# SCH_PCB-device_2024-08-12.net
KiCad netlist of a schematic drawn in EasyEDA
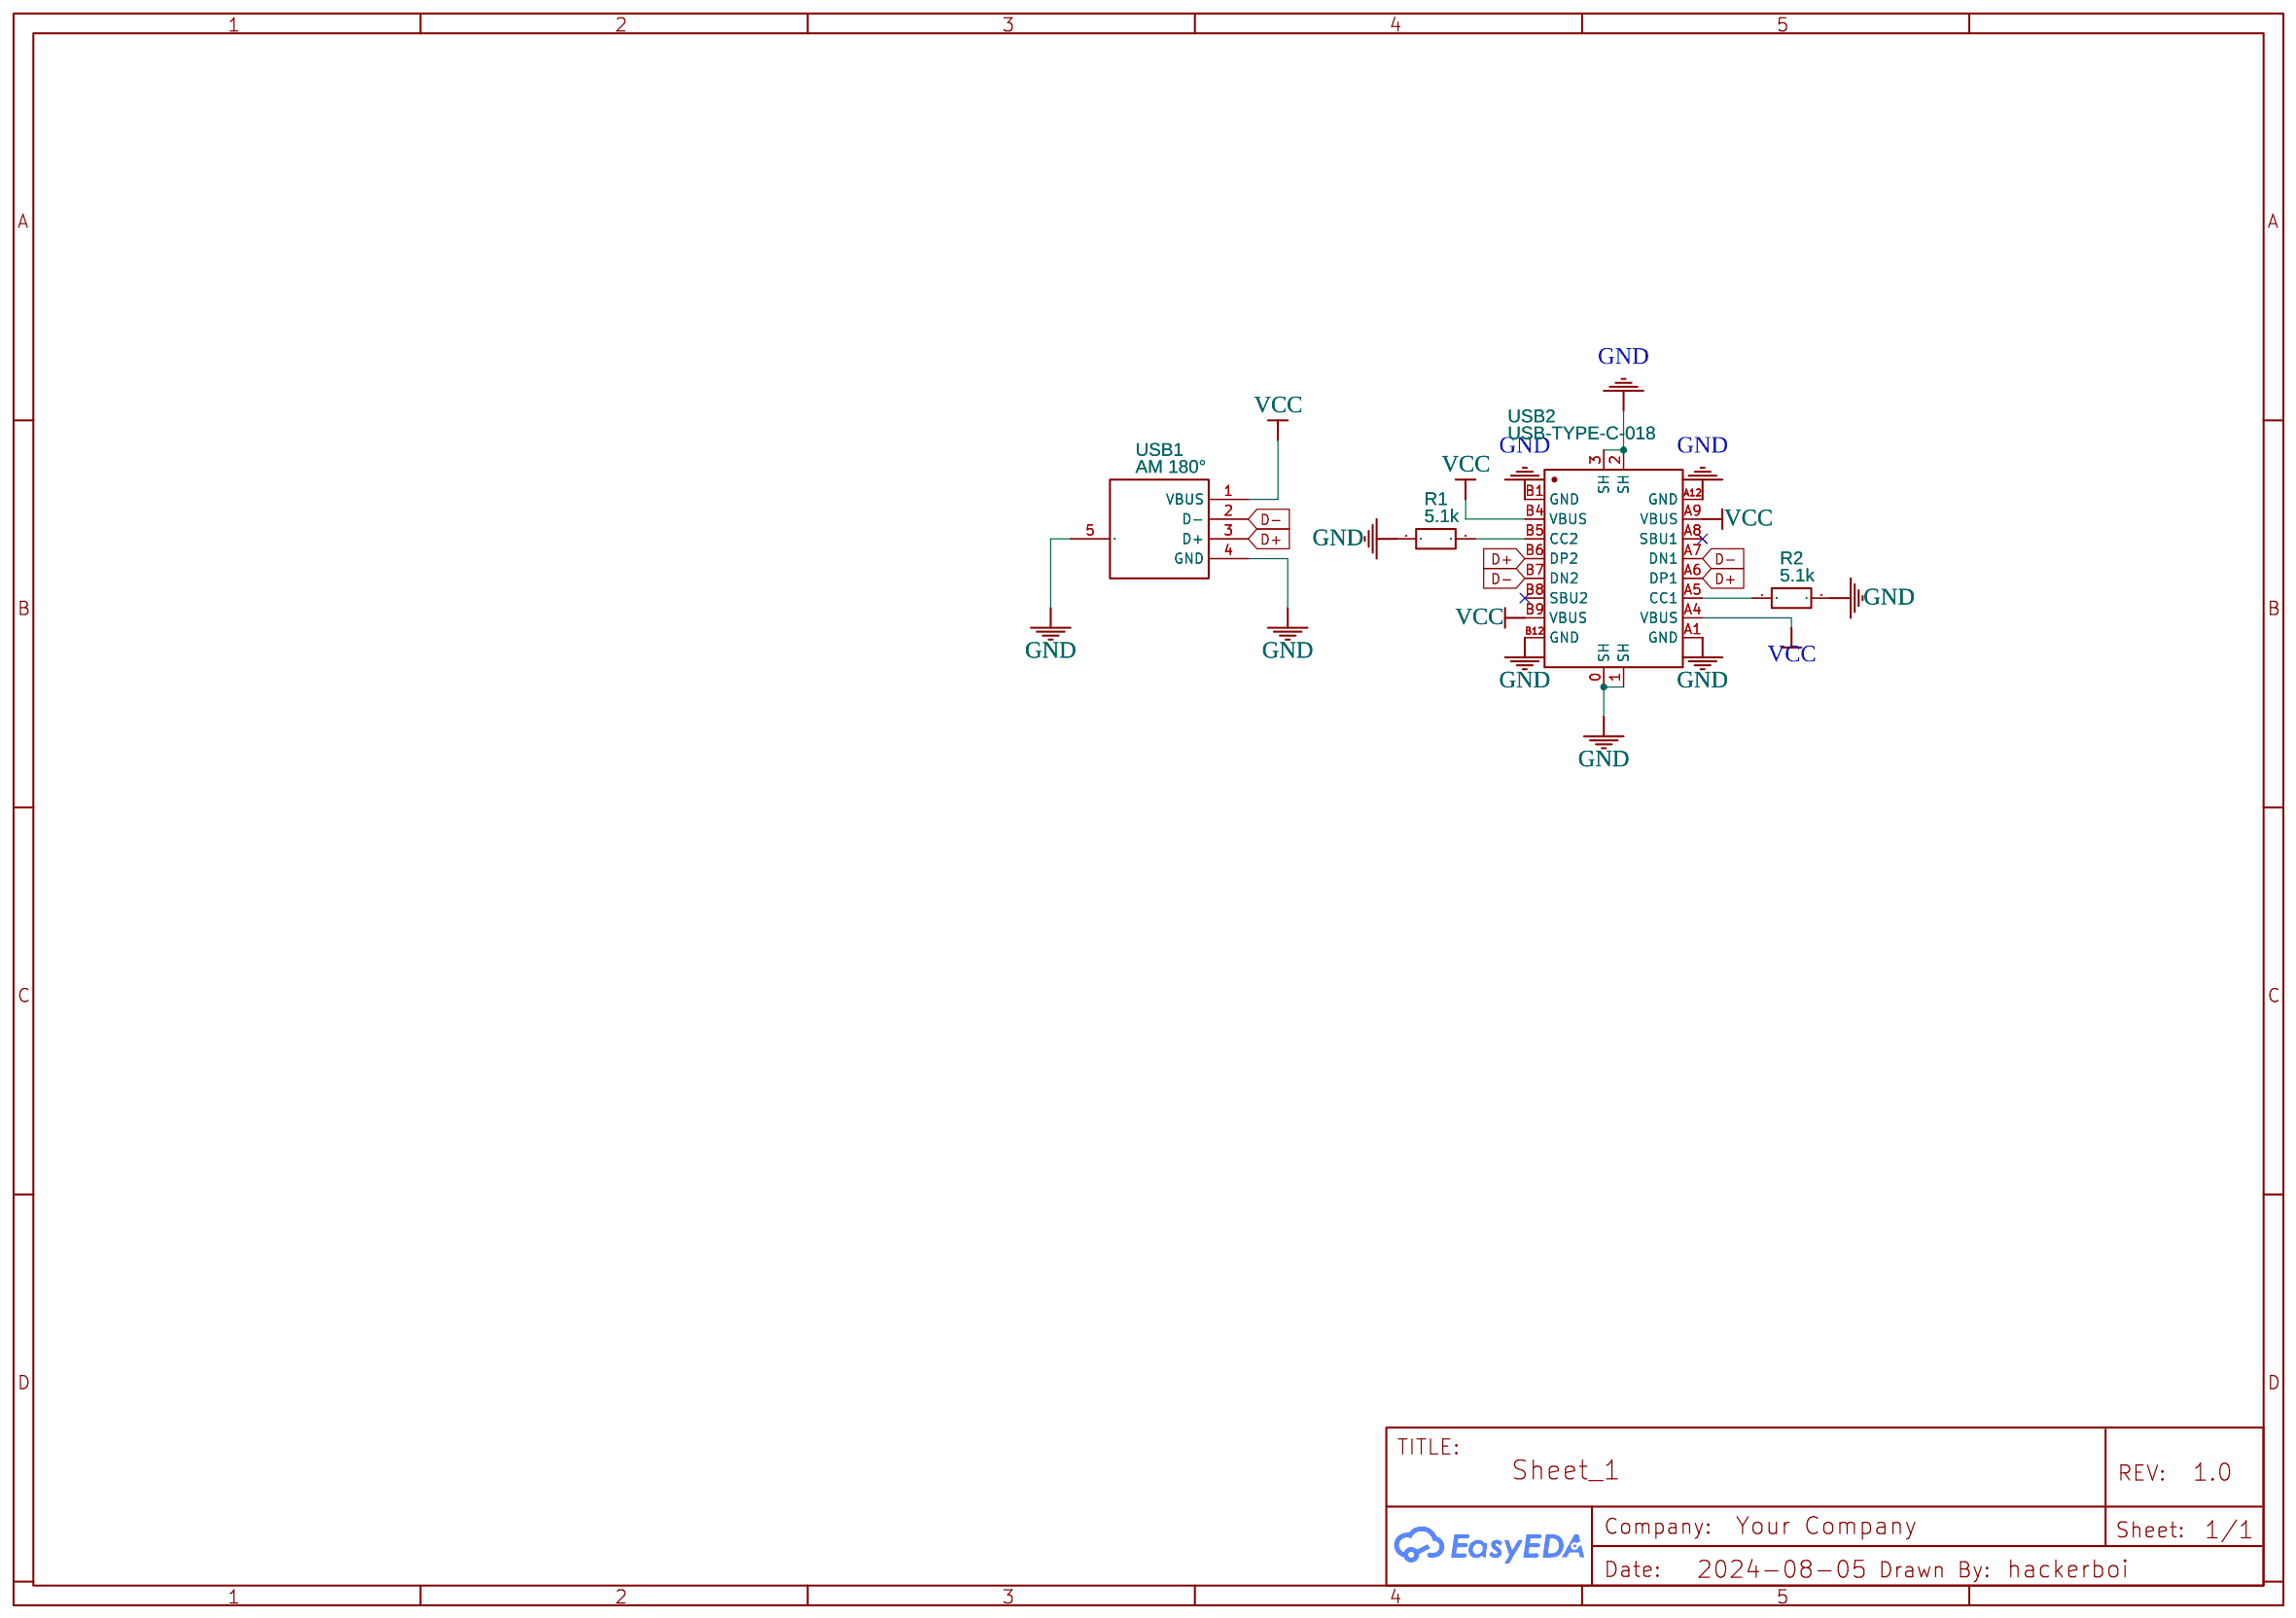
[diagram p0: schematic sheet]

(export (version "E")
  (design (tool "Eeschema 10.0.6"))
  (components
    (comp (ref "R1") (value "5.1k") (libsource (lib "") (part "R_0603_EU")))
    (comp (ref "R2") (value "5.1k") (libsource (lib "") (part "R_0603_EU")))
    (comp (ref "USB1")
      (value "AM 180°")
      (fields (field (name "Manufacturer") "SHOU HAN(首韩)"))
      (libsource (lib "") (part "AM 180°"))
    )
    (comp (ref "USB2")
      (value "USB-TYPE-C-018")
      (fields (field (name "Manufacturer") "DEALON(德艺隆)"))
      (libsource (lib "") (part "USB-TYPE-C-018"))
    )
  )
  (nets
    (net (code "1") (name "D+") (class "Default")
      (node (ref "USB1") (pin "3") (pinfunction "D+_3") (pintype "input"))
      (node (ref "USB2") (pin "A6") (pinfunction "DP1_A6") (pintype "unspecified"))
      (node (ref "USB2") (pin "B6") (pinfunction "DP2_B6") (pintype "unspecified"))
    )
    (net (code "2") (name "D-") (class "Default")
      (node (ref "USB1") (pin "2") (pinfunction "D-_2") (pintype "input"))
      (node (ref "USB2") (pin "A7") (pinfunction "DN1_A7") (pintype "unspecified"))
      (node (ref "USB2") (pin "B7") (pinfunction "DN2_B7") (pintype "unspecified"))
    )
    (net (code "3") (name "GND") (class "Default")
      (node (ref "R1") (pin "1") (pinfunction "1_1") (pintype "unspecified"))
      (node (ref "R2") (pin "2") (pinfunction "2_2") (pintype "unspecified"))
      (node (ref "USB1") (pin "4") (pinfunction "GND_4") (pintype "input"))
      (node (ref "USB1") (pin "5") (pinfunction "EH_5") (pintype "input"))
      (node (ref "USB2") (pin "0") (pinfunction "SH_0") (pintype "unspecified"))
      (node (ref "USB2") (pin "1") (pinfunction "SH_1") (pintype "unspecified"))
      (node (ref "USB2") (pin "2") (pinfunction "SH_2") (pintype "unspecified"))
      (node (ref "USB2") (pin "3") (pinfunction "SH_3") (pintype "unspecified"))
      (node (ref "USB2") (pin "A1") (pinfunction "GND_A1") (pintype "unspecified"))
      (node (ref "USB2") (pin "A12") (pinfunction "GND_A12") (pintype "unspecified"))
      (node (ref "USB2") (pin "B1") (pinfunction "GND_B1") (pintype "unspecified"))
      (node (ref "USB2") (pin "B12") (pinfunction "GND_B12") (pintype "unspecified"))
    )
    (net (code "4") (name "Net-(USB2-CC1)") (class "Default")
      (node (ref "R2") (pin "1") (pinfunction "1_1") (pintype "unspecified"))
      (node (ref "USB2") (pin "A5") (pinfunction "CC1_A5") (pintype "unspecified"))
    )
    (net (code "5") (name "Net-(USB2-CC2)") (class "Default")
      (node (ref "R1") (pin "2") (pinfunction "2_2") (pintype "unspecified"))
      (node (ref "USB2") (pin "B5") (pinfunction "CC2_B5") (pintype "unspecified"))
    )
    (net (code "6") (name "VCC") (class "Default")
      (node (ref "USB1") (pin "1") (pinfunction "VBUS_1") (pintype "input"))
      (node (ref "USB2") (pin "A4") (pinfunction "VBUS_A4") (pintype "unspecified"))
      (node (ref "USB2") (pin "A9") (pinfunction "VBUS_A9") (pintype "unspecified"))
      (node (ref "USB2") (pin "B4") (pinfunction "VBUS_B4") (pintype "unspecified"))
      (node (ref "USB2") (pin "B9") (pinfunction "VBUS_B9") (pintype "unspecified"))
    )
    (net (code "7") (name "unconnected-(USB2-SBU1-PadA8)") (class "Default")
      (node (ref "USB2") (pin "A8") (pinfunction "SBU1_A8") (pintype "unspecified+no_connect"))
    )
    (net (code "8") (name "unconnected-(USB2-SBU2-PadB8)") (class "Default")
      (node (ref "USB2") (pin "B8") (pinfunction "SBU2_B8") (pintype "unspecified+no_connect"))
    )
  )
)
